# RF_ANT_Connector.net
KiCad netlist of a schematic drawn in Altium Designer
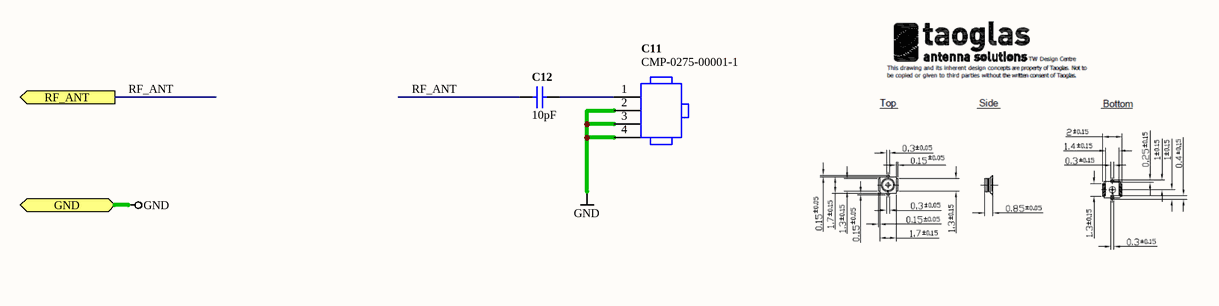
[diagram p0: RF_ANT_Connector.SchDoc]

(export (version "E")
  (design (tool "Eeschema 10.0.6"))
  (components
    (comp (ref "C11")
      (value "CMP-0275-00001-1")
      (footprint "TG-RECE-20369-001E-4_V")
      (description "RF Connector, Onboard Receptacle, IPEX MHFIII")
      (fields (field (name "MANUFACTURER") "Taoglas") (field (name "PARTNUMBER") "RECE-20369-001E-01"))
      (libsource (lib "Altium Content") (part "CMP-0275-00001-1"))
    )
    (comp (ref "C12")
      (value "10pF")
      (footprint "CAPC0402(1005)60_L")
      (description "CAP 10pF 10V ±1% 0402 (1005 Metric) Thickness 0.6mm SMD")
      (fields (field (name "TOLERANCE") "±1%") (field (name "Comment") "CAP 10pF 10V 0402(1005)"))
      (libsource (lib "Altium Content Vault") (part "CMP-1034-00700-1"))
    )
  )
  (nets
    (net (code "1") (name "/RF_ANT") (class "Default")
      (node (ref "C12") (pin "1") (pinfunction "1_1") (pintype "passive"))
    )
    (net (code "2") (name "GND") (class "Default")
      (node (ref "C11") (pin "2") (pinfunction "2_2") (pintype "passive"))
      (node (ref "C11") (pin "3") (pinfunction "3_3") (pintype "passive"))
      (node (ref "C11") (pin "4") (pinfunction "4_4") (pintype "passive"))
    )
    (net (code "3") (name "Net-(C11-Pad1)") (class "Default")
      (node (ref "C11") (pin "1") (pinfunction "1_1") (pintype "passive"))
      (node (ref "C12") (pin "2") (pinfunction "2_2") (pintype "passive"))
    )
  )
)
